# my1.net
KiCad netlist of a schematic drawn in EAGLE
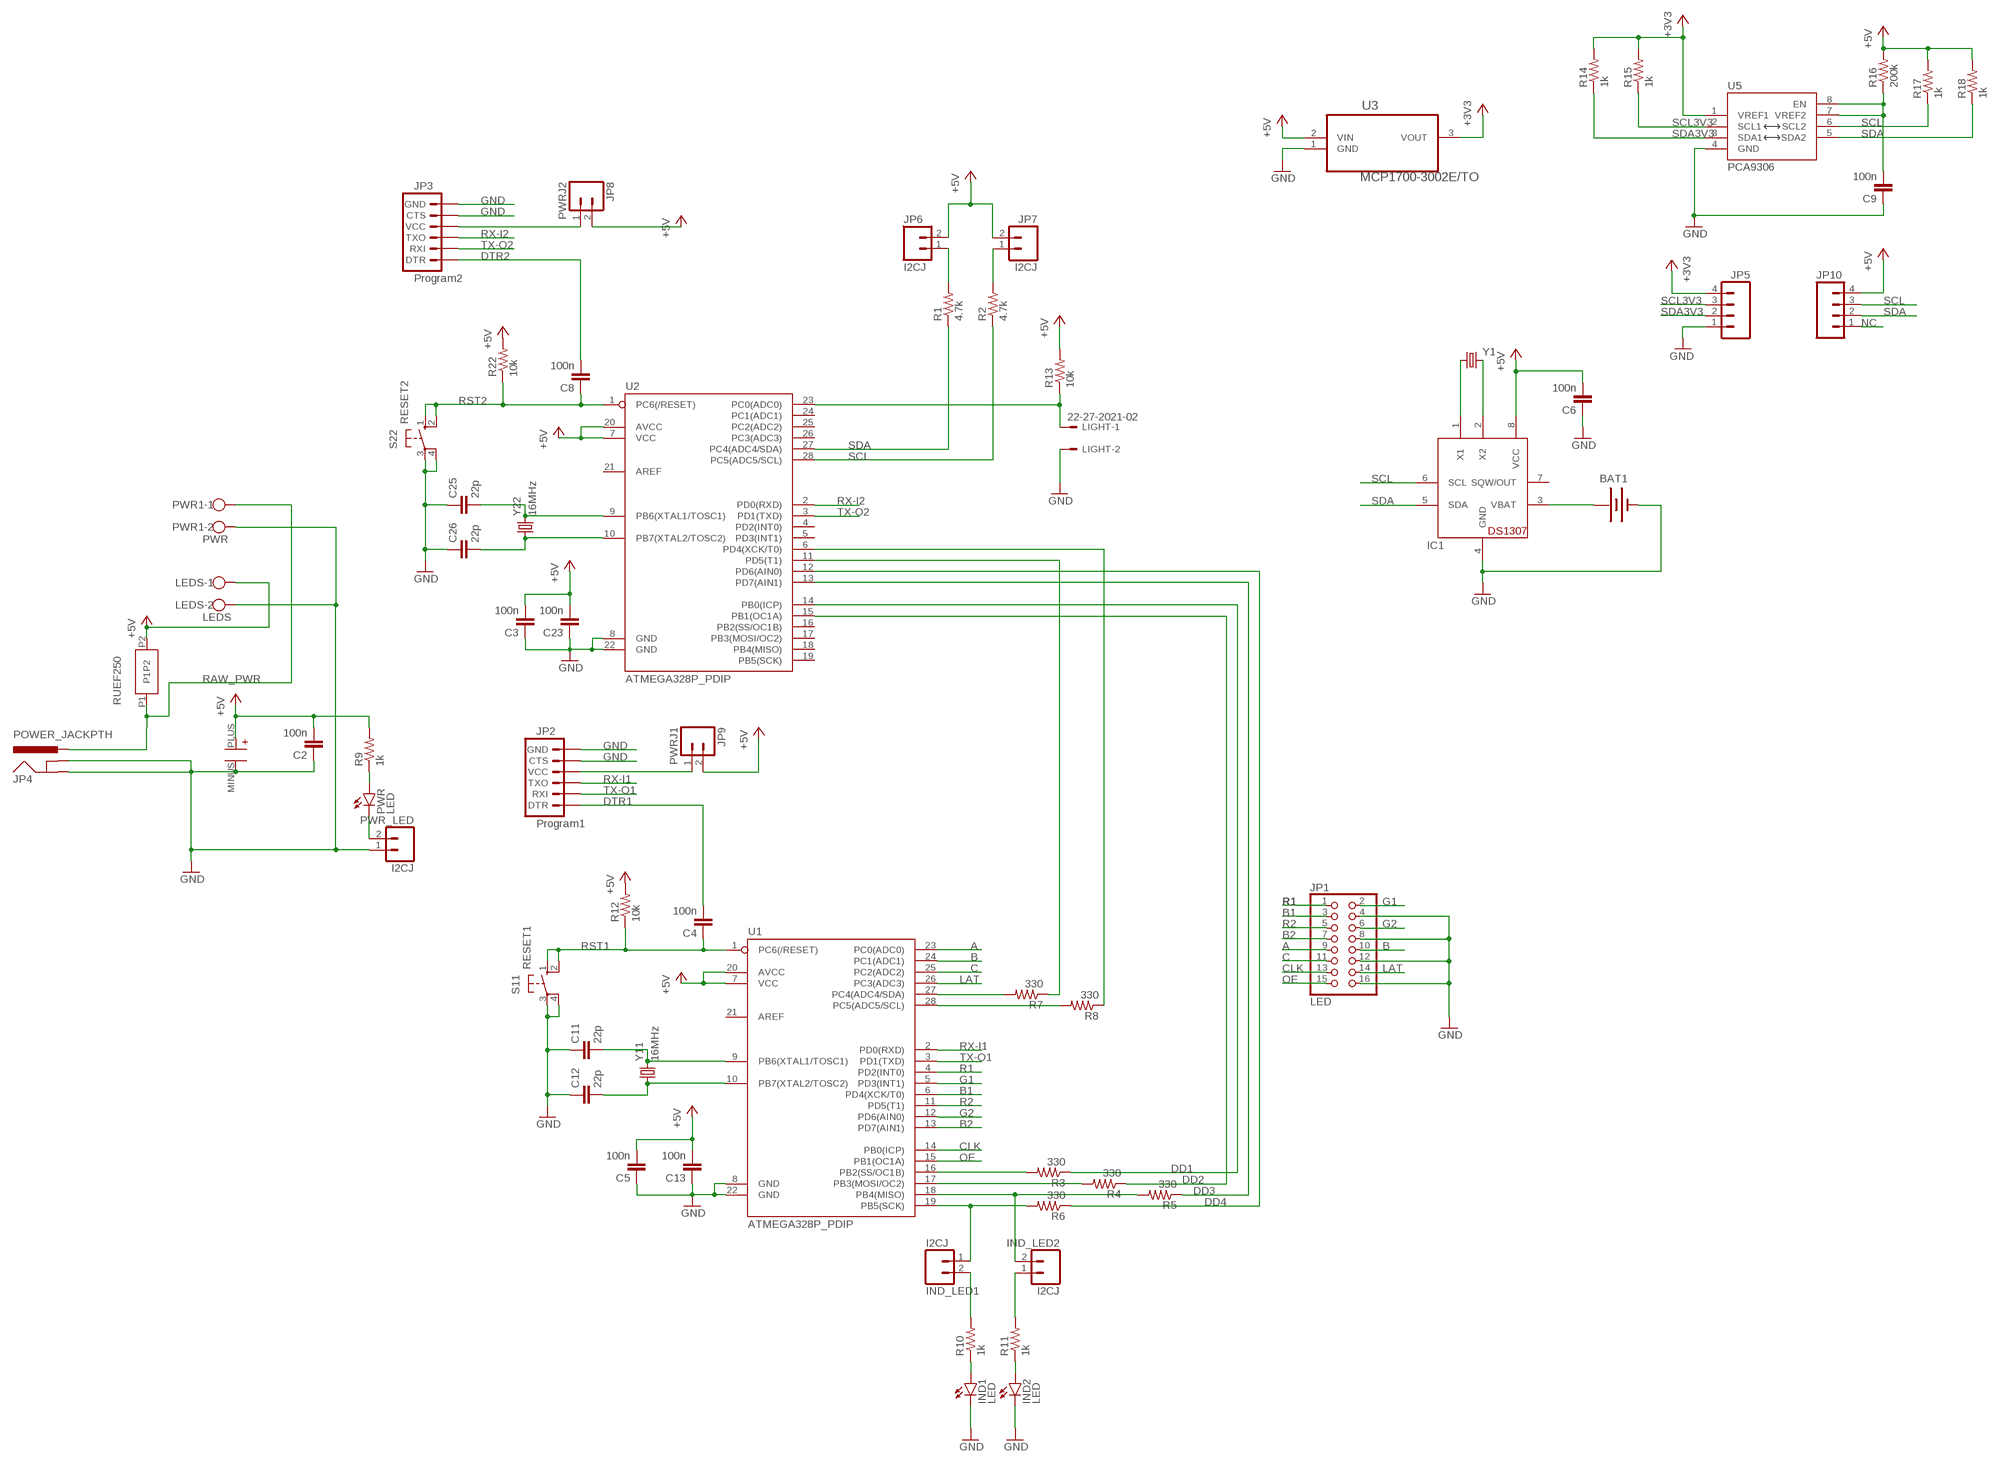
[diagram p0: schematic, sheet 1]

(export (version "E")
  (design (tool "Eeschema 10.0.6"))
  (components
    (comp (ref "BAT1")
      (value "BATTERY12MM")
      (footprint "eagle-import:BATTCON_12MM")
      (libsource (lib "eagle-import") (part "BATTERY12MM"))
    )
    (comp (ref "C1")
      (value "EEU-FR1C471B")
      (footprint "eagle-import:EEU-FR1C471B")
      (libsource (lib "eagle-import") (part "EEU-FR1C471B"))
    )
    (comp (ref "C2")
      (value "100n")
      (footprint "eagle-import:C025-024X044")
      (libsource (lib "eagle-import") (part "C-EU025-024X044"))
    )
    (comp (ref "C3")
      (value "100n")
      (footprint "eagle-import:C025-024X044")
      (libsource (lib "eagle-import") (part "C-EU025-024X044"))
    )
    (comp (ref "C4")
      (value "100n")
      (footprint "eagle-import:C025-024X044")
      (libsource (lib "eagle-import") (part "C-EU025-024X044"))
    )
    (comp (ref "C5")
      (value "100n")
      (footprint "eagle-import:C025-024X044")
      (libsource (lib "eagle-import") (part "C-EU025-024X044"))
    )
    (comp (ref "C6")
      (value "100n")
      (footprint "eagle-import:C025-024X044")
      (libsource (lib "eagle-import") (part "C-EU025-024X044"))
    )
    (comp (ref "C8")
      (value "100n")
      (footprint "eagle-import:C025-024X044")
      (libsource (lib "eagle-import") (part "C-EU025-024X044"))
    )
    (comp (ref "C9")
      (value "100n")
      (footprint "eagle-import:C025-024X044")
      (libsource (lib "eagle-import") (part "C-EU025-024X044"))
    )
    (comp (ref "C11")
      (value "22p")
      (footprint "eagle-import:C025-024X044")
      (libsource (lib "eagle-import") (part "C-EU025-024X044"))
    )
    (comp (ref "C12")
      (value "22p")
      (footprint "eagle-import:C025-024X044")
      (libsource (lib "eagle-import") (part "C-EU025-024X044"))
    )
    (comp (ref "C13")
      (value "100n")
      (footprint "eagle-import:C025-024X044")
      (libsource (lib "eagle-import") (part "C-EU025-024X044"))
    )
    (comp (ref "C23")
      (value "100n")
      (footprint "eagle-import:C025-024X044")
      (libsource (lib "eagle-import") (part "C-EU025-024X044"))
    )
    (comp (ref "C25")
      (value "22p")
      (footprint "eagle-import:C025-024X044")
      (libsource (lib "eagle-import") (part "C-EU025-024X044"))
    )
    (comp (ref "C26")
      (value "22p")
      (footprint "eagle-import:C025-024X044")
      (libsource (lib "eagle-import") (part "C-EU025-024X044"))
    )
    (comp (ref "IC1")
      (value "DS1307")
      (footprint "eagle-import:DIL08")
      (libsource (lib "eagle-import") (part "DS1307"))
    )
    (comp (ref "IND1")
      (value "LED")
      (footprint "eagle-import:LED5MM")
      (libsource (lib "eagle-import") (part "LED5MM"))
    )
    (comp (ref "IND2")
      (value "LED")
      (footprint "eagle-import:LED5MM")
      (libsource (lib "eagle-import") (part "LED5MM"))
    )
    (comp (ref "IND_LED1")
      (value "I2CJ")
      (footprint "eagle-import:1X02")
      (libsource (lib "eagle-import") (part "M02PTH"))
    )
    (comp (ref "IND_LED2")
      (value "I2CJ")
      (footprint "eagle-import:1X02")
      (libsource (lib "eagle-import") (part "M02PTH"))
    )
    (comp (ref "JP1")
      (value "LED")
      (footprint "eagle-import:2X08")
      (libsource (lib "eagle-import") (part "PINHD-2X8"))
    )
    (comp (ref "JP2")
      (value "Program1")
      (footprint "eagle-import:1X06")
      (libsource (lib "eagle-import") (part "ARDUINO_SERIAL_PROGRAMPTH"))
    )
    (comp (ref "JP3")
      (value "Program2")
      (footprint "eagle-import:1X06")
      (libsource (lib "eagle-import") (part "ARDUINO_SERIAL_PROGRAMPTH"))
    )
    (comp (ref "JP4")
      (value "POWER_JACKPTH")
      (footprint "eagle-import:POWER_JACK_PTH")
      (libsource (lib "eagle-import") (part "POWER_JACKPTH"))
    )
    (comp (ref "JP5")
      (value "M04PTH")
      (footprint "eagle-import:1X04")
      (libsource (lib "eagle-import") (part "M04PTH"))
    )
    (comp (ref "JP6")
      (value "I2CJ")
      (footprint "eagle-import:1X02")
      (libsource (lib "eagle-import") (part "M02PTH"))
    )
    (comp (ref "JP7")
      (value "I2CJ")
      (footprint "eagle-import:1X02")
      (libsource (lib "eagle-import") (part "M02PTH"))
    )
    (comp (ref "JP8")
      (value "PWRJ2")
      (footprint "eagle-import:1X02")
      (libsource (lib "eagle-import") (part "M02PTH"))
    )
    (comp (ref "JP9")
      (value "PWRJ1")
      (footprint "eagle-import:1X02")
      (libsource (lib "eagle-import") (part "M02PTH"))
    )
    (comp (ref "JP10")
      (value "M04PTH")
      (footprint "eagle-import:1X04")
      (libsource (lib "eagle-import") (part "M04PTH"))
    )
    (comp (ref "LEDS")
      (value "LEDS")
      (footprint "eagle-import:W237-102")
      (fields (field (name "MPN") "237-102"))
      (libsource (lib "eagle-import") (part "W237-102"))
    )
    (comp (ref "LIGHT")
      (value "22-27-2021-02")
      (footprint "eagle-import:6410-02")
      (libsource (lib "eagle-import") (part "22-?-0227-2021"))
    )
    (comp (ref "PWR")
      (value "LED")
      (footprint "eagle-import:LED5MM")
      (libsource (lib "eagle-import") (part "LED5MM"))
    )
    (comp (ref "PWR1")
      (value "PWR")
      (footprint "eagle-import:W237-102")
      (fields (field (name "MPN") "237-102"))
      (libsource (lib "eagle-import") (part "W237-102"))
    )
    (comp (ref "PWR_LED")
      (value "I2CJ")
      (footprint "eagle-import:1X02")
      (libsource (lib "eagle-import") (part "M02PTH"))
    )
    (comp (ref "R1")
      (value "4.7k")
      (footprint "eagle-import:AXIAL-0.3")
      (libsource (lib "eagle-import") (part "RESISTORAXIAL-0.3"))
    )
    (comp (ref "R2")
      (value "4.7k")
      (footprint "eagle-import:AXIAL-0.3")
      (libsource (lib "eagle-import") (part "RESISTORAXIAL-0.3"))
    )
    (comp (ref "R3")
      (value "330")
      (footprint "eagle-import:AXIAL-0.3")
      (libsource (lib "eagle-import") (part "RESISTORAXIAL-0.3"))
    )
    (comp (ref "R4")
      (value "330")
      (footprint "eagle-import:AXIAL-0.3")
      (libsource (lib "eagle-import") (part "RESISTORAXIAL-0.3"))
    )
    (comp (ref "R5")
      (value "330")
      (footprint "eagle-import:AXIAL-0.3")
      (libsource (lib "eagle-import") (part "RESISTORAXIAL-0.3"))
    )
    (comp (ref "R6")
      (value "330")
      (footprint "eagle-import:AXIAL-0.3")
      (libsource (lib "eagle-import") (part "RESISTORAXIAL-0.3"))
    )
    (comp (ref "R7")
      (value "330")
      (footprint "eagle-import:AXIAL-0.3")
      (libsource (lib "eagle-import") (part "RESISTORAXIAL-0.3"))
    )
    (comp (ref "R8")
      (value "330")
      (footprint "eagle-import:AXIAL-0.3")
      (libsource (lib "eagle-import") (part "RESISTORAXIAL-0.3"))
    )
    (comp (ref "R9")
      (value "1k")
      (footprint "eagle-import:AXIAL-0.3")
      (libsource (lib "eagle-import") (part "RESISTORAXIAL-0.3"))
    )
    (comp (ref "R10")
      (value "1k")
      (footprint "eagle-import:AXIAL-0.3")
      (libsource (lib "eagle-import") (part "RESISTORAXIAL-0.3"))
    )
    (comp (ref "R11")
      (value "1k")
      (footprint "eagle-import:AXIAL-0.3")
      (libsource (lib "eagle-import") (part "RESISTORAXIAL-0.3"))
    )
    (comp (ref "R12")
      (value "10k")
      (footprint "eagle-import:AXIAL-0.3")
      (libsource (lib "eagle-import") (part "RESISTORAXIAL-0.3"))
    )
    (comp (ref "R13")
      (value "10k")
      (footprint "eagle-import:AXIAL-0.3")
      (libsource (lib "eagle-import") (part "RESISTORAXIAL-0.3"))
    )
    (comp (ref "R14")
      (value "1k")
      (footprint "eagle-import:AXIAL-0.3")
      (libsource (lib "eagle-import") (part "RESISTORAXIAL-0.3"))
    )
    (comp (ref "R15")
      (value "1k")
      (footprint "eagle-import:AXIAL-0.3")
      (libsource (lib "eagle-import") (part "RESISTORAXIAL-0.3"))
    )
    (comp (ref "R16")
      (value "200k")
      (footprint "eagle-import:AXIAL-0.3")
      (libsource (lib "eagle-import") (part "RESISTORAXIAL-0.3"))
    )
    (comp (ref "R17")
      (value "1k")
      (footprint "eagle-import:AXIAL-0.3")
      (libsource (lib "eagle-import") (part "RESISTORAXIAL-0.3"))
    )
    (comp (ref "R18")
      (value "1k")
      (footprint "eagle-import:AXIAL-0.3")
      (libsource (lib "eagle-import") (part "RESISTORAXIAL-0.3"))
    )
    (comp (ref "R22")
      (value "10k")
      (footprint "eagle-import:AXIAL-0.3")
      (libsource (lib "eagle-import") (part "RESISTORAXIAL-0.3"))
    )
    (comp (ref "RUEF250")
      (value "RUEF250U")
      (footprint "eagle-import:RUEF250U")
      (libsource (lib "eagle-import") (part "RUEF250U"))
    )
    (comp (ref "S11")
      (value "RESET1")
      (footprint "eagle-import:B3F-10XX")
      (fields (field (name "MPN") "B3F-1000"))
      (libsource (lib "eagle-import") (part "10-XX"))
    )
    (comp (ref "S22")
      (value "RESET2")
      (footprint "eagle-import:B3F-10XX")
      (fields (field (name "MPN") "B3F-1000"))
      (libsource (lib "eagle-import") (part "10-XX"))
    )
    (comp (ref "U1")
      (value "ATMEGA328P_PDIP")
      (footprint "eagle-import:DIL28-3")
      (libsource (lib "eagle-import") (part "ATMEGA328P_PDIP"))
    )
    (comp (ref "U2")
      (value "ATMEGA328P_PDIP")
      (footprint "eagle-import:DIL28-3")
      (libsource (lib "eagle-import") (part "ATMEGA328P_PDIP"))
    )
    (comp (ref "U3")
      (value "MCP1700-3002E/TO")
      (footprint "eagle-import:TO127P254X495-3")
      (libsource (lib "eagle-import") (part "MCP1700-3002E/TO"))
    )
    (comp (ref "U5")
      (value "PCA9306")
      (footprint "eagle-import:PSOP-8")
      (libsource (lib "eagle-import") (part "PCA9306"))
    )
    (comp (ref "Y1")
      (value "CRYSTAL32-SMD")
      (footprint "eagle-import:CRYSTAL-32KHZ-SMD")
      (libsource (lib "eagle-import") (part "CRYSTAL32-SMD"))
    )
    (comp (ref "Y11")
      (value "16MHz")
      (footprint "eagle-import:HC49US")
      (libsource (lib "eagle-import") (part "CRYSTALHC49US"))
    )
    (comp (ref "Y22")
      (value "16MHz")
      (footprint "eagle-import:HC49US")
      (libsource (lib "eagle-import") (part "CRYSTALHC49US"))
    )
  )
  (nets
    (net (code "1") (name "+3V3") (class "Default")
      (node (ref "JP5") (pin "4") (pinfunction "4_4") (pintype "passive"))
      (node (ref "R14") (pin "P$2") (pinfunction "2_P$2") (pintype "passive"))
      (node (ref "R15") (pin "P$2") (pinfunction "2_P$2") (pintype "passive"))
      (node (ref "U3") (pin "3") (pinfunction "VOUT_3") (pintype "output"))
      (node (ref "U5") (pin "1") (pinfunction "VREF1_1") (pintype "bidirectional"))
    )
    (net (code "2") (name "+5V") (class "Default")
      (node (ref "C1") (pin "PLUS") (pinfunction "PLUS_PLUS") (pintype "bidirectional"))
      (node (ref "C13") (pin "2") (pinfunction "2_2") (pintype "passive"))
      (node (ref "C2") (pin "2") (pinfunction "2_2") (pintype "passive"))
      (node (ref "C23") (pin "2") (pinfunction "2_2") (pintype "passive"))
      (node (ref "C3") (pin "2") (pinfunction "2_2") (pintype "passive"))
      (node (ref "C5") (pin "2") (pinfunction "2_2") (pintype "passive"))
      (node (ref "C6") (pin "2") (pinfunction "2_2") (pintype "passive"))
      (node (ref "IC1") (pin "8") (pinfunction "VCC_8") (pintype "power_in"))
      (node (ref "JP10") (pin "4") (pinfunction "4_4") (pintype "passive"))
      (node (ref "JP6") (pin "2") (pinfunction "2_2") (pintype "passive"))
      (node (ref "JP7") (pin "2") (pinfunction "2_2") (pintype "passive"))
      (node (ref "JP8") (pin "2") (pinfunction "2_2") (pintype "passive"))
      (node (ref "JP9") (pin "2") (pinfunction "2_2") (pintype "passive"))
      (node (ref "LEDS") (pin "1") (pinfunction "KL_1") (pintype "passive"))
      (node (ref "R12") (pin "P$2") (pinfunction "2_P$2") (pintype "passive"))
      (node (ref "R13") (pin "P$2") (pinfunction "2_P$2") (pintype "passive"))
      (node (ref "R16") (pin "P$2") (pinfunction "2_P$2") (pintype "passive"))
      (node (ref "R17") (pin "P$2") (pinfunction "2_P$2") (pintype "passive"))
      (node (ref "R18") (pin "P$2") (pinfunction "2_P$2") (pintype "passive"))
      (node (ref "R22") (pin "P$2") (pinfunction "2_P$2") (pintype "passive"))
      (node (ref "R9") (pin "P$2") (pinfunction "2_P$2") (pintype "passive"))
      (node (ref "RUEF250") (pin "P2") (pinfunction "P2_P2") (pintype "bidirectional"))
      (node (ref "U1") (pin "20") (pinfunction "AVCC_20") (pintype "bidirectional"))
      (node (ref "U1") (pin "7") (pinfunction "VCC_7") (pintype "bidirectional"))
      (node (ref "U2") (pin "20") (pinfunction "AVCC_20") (pintype "bidirectional"))
      (node (ref "U2") (pin "7") (pinfunction "VCC_7") (pintype "bidirectional"))
      (node (ref "U3") (pin "2") (pinfunction "VIN_2") (pintype "input"))
    )
    (net (code "3") (name "/A") (class "Default")
      (node (ref "JP1") (pin "9") (pinfunction "9_9") (pintype "passive"))
      (node (ref "U1") (pin "23") (pinfunction "PC0(ADC0)_23") (pintype "bidirectional"))
    )
    (net (code "4") (name "/B") (class "Default")
      (node (ref "JP1") (pin "10") (pinfunction "10_10") (pintype "passive"))
      (node (ref "U1") (pin "24") (pinfunction "PC1(ADC1)_24") (pintype "bidirectional"))
    )
    (net (code "5") (name "/B1") (class "Default")
      (node (ref "JP1") (pin "3") (pinfunction "3_3") (pintype "passive"))
      (node (ref "U1") (pin "6") (pinfunction "PD4(XCK/T0)_6") (pintype "bidirectional"))
    )
    (net (code "6") (name "/B2") (class "Default")
      (node (ref "JP1") (pin "7") (pinfunction "7_7") (pintype "passive"))
      (node (ref "U1") (pin "13") (pinfunction "PD7(AIN1)_13") (pintype "bidirectional"))
    )
    (net (code "7") (name "/C") (class "Default")
      (node (ref "JP1") (pin "11") (pinfunction "11_11") (pintype "passive"))
      (node (ref "U1") (pin "25") (pinfunction "PC2(ADC2)_25") (pintype "bidirectional"))
    )
    (net (code "8") (name "/CLK") (class "Default")
      (node (ref "JP1") (pin "13") (pinfunction "13_13") (pintype "passive"))
      (node (ref "U1") (pin "14") (pinfunction "PB0(ICP)_14") (pintype "bidirectional"))
    )
    (net (code "9") (name "/DD1") (class "Default")
      (node (ref "R3") (pin "P$1") (pinfunction "1_P$1") (pintype "passive"))
      (node (ref "U2") (pin "14") (pinfunction "PB0(ICP)_14") (pintype "bidirectional"))
    )
    (net (code "10") (name "/DD2") (class "Default")
      (node (ref "R4") (pin "P$1") (pinfunction "1_P$1") (pintype "passive"))
      (node (ref "U2") (pin "15") (pinfunction "PB1(OC1A)_15") (pintype "bidirectional"))
    )
    (net (code "11") (name "/DD3") (class "Default")
      (node (ref "R5") (pin "P$1") (pinfunction "1_P$1") (pintype "passive"))
      (node (ref "U2") (pin "13") (pinfunction "PD7(AIN1)_13") (pintype "bidirectional"))
    )
    (net (code "12") (name "/DD4") (class "Default")
      (node (ref "R6") (pin "P$1") (pinfunction "1_P$1") (pintype "passive"))
      (node (ref "U2") (pin "12") (pinfunction "PD6(AIN0)_12") (pintype "bidirectional"))
    )
    (net (code "13") (name "/DTR1") (class "Default")
      (node (ref "C4") (pin "2") (pinfunction "2_2") (pintype "passive"))
      (node (ref "JP2") (pin "1") (pinfunction "DTR_1") (pintype "passive"))
    )
    (net (code "14") (name "/DTR2") (class "Default")
      (node (ref "C8") (pin "2") (pinfunction "2_2") (pintype "passive"))
      (node (ref "JP3") (pin "1") (pinfunction "DTR_1") (pintype "passive"))
    )
    (net (code "15") (name "/G1") (class "Default")
      (node (ref "JP1") (pin "2") (pinfunction "2_2") (pintype "passive"))
      (node (ref "U1") (pin "5") (pinfunction "PD3(INT1)_5") (pintype "bidirectional"))
    )
    (net (code "16") (name "/G2") (class "Default")
      (node (ref "JP1") (pin "6") (pinfunction "6_6") (pintype "passive"))
      (node (ref "U1") (pin "12") (pinfunction "PD6(AIN0)_12") (pintype "bidirectional"))
    )
    (net (code "17") (name "/LAT") (class "Default")
      (node (ref "JP1") (pin "14") (pinfunction "14_14") (pintype "passive"))
      (node (ref "U1") (pin "26") (pinfunction "PC3(ADC3)_26") (pintype "bidirectional"))
    )
    (net (code "18") (name "/NC") (class "Default")
      (node (ref "JP10") (pin "1") (pinfunction "1_1") (pintype "passive"))
    )
    (net (code "19") (name "/OE") (class "Default")
      (node (ref "JP1") (pin "15") (pinfunction "15_15") (pintype "passive"))
      (node (ref "U1") (pin "15") (pinfunction "PB1(OC1A)_15") (pintype "bidirectional"))
    )
    (net (code "20") (name "/R1") (class "Default")
      (node (ref "JP1") (pin "1") (pinfunction "1_1") (pintype "passive"))
      (node (ref "U1") (pin "4") (pinfunction "PD2(INT0)_4") (pintype "bidirectional"))
    )
    (net (code "21") (name "/R2") (class "Default")
      (node (ref "JP1") (pin "5") (pinfunction "5_5") (pintype "passive"))
      (node (ref "U1") (pin "11") (pinfunction "PD5(T1)_11") (pintype "bidirectional"))
    )
    (net (code "22") (name "/RAW_PWR") (class "Default")
      (node (ref "JP4") (pin "PWR") (pinfunction "PWR_PWR") (pintype "bidirectional"))
      (node (ref "PWR1") (pin "1") (pinfunction "KL_1") (pintype "passive"))
      (node (ref "RUEF250") (pin "P1") (pinfunction "P1_P1") (pintype "bidirectional"))
    )
    (net (code "23") (name "/RST1") (class "Default")
      (node (ref "C4") (pin "1") (pinfunction "1_1") (pintype "passive"))
      (node (ref "R12") (pin "P$1") (pinfunction "1_P$1") (pintype "passive"))
      (node (ref "S11") (pin "1") (pinfunction "S_1") (pintype "passive"))
      (node (ref "S11") (pin "2") (pinfunction "S1_2") (pintype "passive"))
      (node (ref "U1") (pin "1") (pinfunction "PC6(/RESET)_1") (pintype "bidirectional"))
    )
    (net (code "24") (name "/RST2") (class "Default")
      (node (ref "C8") (pin "1") (pinfunction "1_1") (pintype "passive"))
      (node (ref "R22") (pin "P$1") (pinfunction "1_P$1") (pintype "passive"))
      (node (ref "S22") (pin "1") (pinfunction "S_1") (pintype "passive"))
      (node (ref "S22") (pin "2") (pinfunction "S1_2") (pintype "passive"))
      (node (ref "U2") (pin "1") (pinfunction "PC6(/RESET)_1") (pintype "bidirectional"))
    )
    (net (code "25") (name "/RX-I1") (class "Default")
      (node (ref "JP2") (pin "3") (pinfunction "TXO_3") (pintype "passive"))
      (node (ref "U1") (pin "2") (pinfunction "PD0(RXD)_2") (pintype "bidirectional"))
    )
    (net (code "26") (name "/RX-I2") (class "Default")
      (node (ref "JP3") (pin "3") (pinfunction "TXO_3") (pintype "passive"))
      (node (ref "U2") (pin "2") (pinfunction "PD0(RXD)_2") (pintype "bidirectional"))
    )
    (net (code "27") (name "/SCL") (class "Default")
      (node (ref "IC1") (pin "6") (pinfunction "SCL_6") (pintype "bidirectional"))
      (node (ref "JP10") (pin "3") (pinfunction "3_3") (pintype "passive"))
      (node (ref "R17") (pin "P$1") (pinfunction "1_P$1") (pintype "passive"))
      (node (ref "R2") (pin "P$1") (pinfunction "1_P$1") (pintype "passive"))
      (node (ref "U2") (pin "28") (pinfunction "PC5(ADC5/SCL)_28") (pintype "bidirectional"))
      (node (ref "U5") (pin "6") (pinfunction "SCL2_6") (pintype "bidirectional"))
    )
    (net (code "28") (name "/SCL3V3") (class "Default")
      (node (ref "JP5") (pin "3") (pinfunction "3_3") (pintype "passive"))
      (node (ref "R15") (pin "P$1") (pinfunction "1_P$1") (pintype "passive"))
      (node (ref "U5") (pin "2") (pinfunction "SCL1_2") (pintype "bidirectional"))
    )
    (net (code "29") (name "/SDA") (class "Default")
      (node (ref "IC1") (pin "5") (pinfunction "SDA_5") (pintype "bidirectional"))
      (node (ref "JP10") (pin "2") (pinfunction "2_2") (pintype "passive"))
      (node (ref "R1") (pin "P$1") (pinfunction "1_P$1") (pintype "passive"))
      (node (ref "R18") (pin "P$1") (pinfunction "1_P$1") (pintype "passive"))
      (node (ref "U2") (pin "27") (pinfunction "PC4(ADC4/SDA)_27") (pintype "bidirectional"))
      (node (ref "U5") (pin "5") (pinfunction "SDA2_5") (pintype "bidirectional"))
    )
    (net (code "30") (name "/SDA3V3") (class "Default")
      (node (ref "JP5") (pin "2") (pinfunction "2_2") (pintype "passive"))
      (node (ref "R14") (pin "P$1") (pinfunction "1_P$1") (pintype "passive"))
      (node (ref "U5") (pin "3") (pinfunction "SDA1_3") (pintype "bidirectional"))
    )
    (net (code "31") (name "/TX-O1") (class "Default")
      (node (ref "JP2") (pin "2") (pinfunction "RXI_2") (pintype "passive"))
      (node (ref "U1") (pin "3") (pinfunction "PD1(TXD)_3") (pintype "bidirectional"))
    )
    (net (code "32") (name "/TX-O2") (class "Default")
      (node (ref "JP3") (pin "2") (pinfunction "RXI_2") (pintype "passive"))
      (node (ref "U2") (pin "3") (pinfunction "PD1(TXD)_3") (pintype "bidirectional"))
    )
    (net (code "33") (name "GND") (class "Default")
      (node (ref "BAT1") (pin "GND") (pinfunction "-_GND") (pintype "power_in"))
      (node (ref "C1") (pin "MINUS") (pinfunction "MINUS_MINUS") (pintype "bidirectional"))
      (node (ref "C11") (pin "1") (pinfunction "1_1") (pintype "passive"))
      (node (ref "C12") (pin "1") (pinfunction "1_1") (pintype "passive"))
      (node (ref "C13") (pin "1") (pinfunction "1_1") (pintype "passive"))
      (node (ref "C2") (pin "1") (pinfunction "1_1") (pintype "passive"))
      (node (ref "C23") (pin "1") (pinfunction "1_1") (pintype "passive"))
      (node (ref "C25") (pin "1") (pinfunction "1_1") (pintype "passive"))
      (node (ref "C26") (pin "1") (pinfunction "1_1") (pintype "passive"))
      (node (ref "C3") (pin "1") (pinfunction "1_1") (pintype "passive"))
      (node (ref "C5") (pin "1") (pinfunction "1_1") (pintype "passive"))
      (node (ref "C6") (pin "1") (pinfunction "1_1") (pintype "passive"))
      (node (ref "C9") (pin "1") (pinfunction "1_1") (pintype "passive"))
      (node (ref "IC1") (pin "4") (pinfunction "GND_4") (pintype "power_in"))
      (node (ref "IND1") (pin "K") (pinfunction "C_K") (pintype "passive"))
      (node (ref "IND2") (pin "K") (pinfunction "C_K") (pintype "passive"))
      (node (ref "JP1") (pin "12") (pinfunction "12_12") (pintype "passive"))
      (node (ref "JP1") (pin "16") (pinfunction "16_16") (pintype "passive"))
      (node (ref "JP1") (pin "4") (pinfunction "4_4") (pintype "passive"))
      (node (ref "JP1") (pin "8") (pinfunction "8_8") (pintype "passive"))
      (node (ref "JP2") (pin "5") (pinfunction "CTS_5") (pintype "passive"))
      (node (ref "JP2") (pin "6") (pinfunction "GND_6") (pintype "passive"))
      (node (ref "JP3") (pin "5") (pinfunction "CTS_5") (pintype "passive"))
      (node (ref "JP3") (pin "6") (pinfunction "GND_6") (pintype "passive"))
      (node (ref "JP4") (pin "GND") (pinfunction "GND_GND") (pintype "bidirectional"))
      (node (ref "JP4") (pin "GNDBREAK") (pinfunction "GNDBREAK_GNDBREAK") (pintype "bidirectional"))
      (node (ref "JP5") (pin "1") (pinfunction "1_1") (pintype "passive"))
      (node (ref "LEDS") (pin "2") (pinfunction "KL_2") (pintype "passive"))
      (node (ref "LIGHT") (pin "2") (pinfunction "S_2") (pintype "passive"))
      (node (ref "PWR1") (pin "2") (pinfunction "KL_2") (pintype "passive"))
      (node (ref "PWR_LED") (pin "1") (pinfunction "1_1") (pintype "passive"))
      (node (ref "S11") (pin "3") (pinfunction "P_3") (pintype "passive"))
      (node (ref "S11") (pin "4") (pinfunction "P1_4") (pintype "passive"))
      (node (ref "S22") (pin "3") (pinfunction "P_3") (pintype "passive"))
      (node (ref "S22") (pin "4") (pinfunction "P1_4") (pintype "passive"))
      (node (ref "U1") (pin "22") (pinfunction "GND_22") (pintype "bidirectional"))
      (node (ref "U1") (pin "8") (pinfunction "GND_8") (pintype "bidirectional"))
      (node (ref "U2") (pin "22") (pinfunction "GND_22") (pintype "bidirectional"))
      (node (ref "U2") (pin "8") (pinfunction "GND_8") (pintype "bidirectional"))
      (node (ref "U3") (pin "1") (pinfunction "GND_1") (pintype "passive"))
      (node (ref "U5") (pin "4") (pinfunction "GND_4") (pintype "bidirectional"))
    )
    (net (code "34") (name "Net-(BAT1-+)") (class "Default")
      (node (ref "BAT1") (pin "PWR@1") (pinfunction "+_PWR@1") (pintype "power_in"))
      (node (ref "IC1") (pin "3") (pinfunction "VBAT_3") (pintype "power_in"))
    )
    (net (code "35") (name "Net-(IC1-X1)") (class "Default")
      (node (ref "IC1") (pin "1") (pinfunction "X1_1") (pintype "passive"))
      (node (ref "Y1") (pin "X1") (pinfunction "1_X1") (pintype "passive"))
    )
    (net (code "36") (name "Net-(IC1-X2)") (class "Default")
      (node (ref "IC1") (pin "2") (pinfunction "X2_2") (pintype "passive"))
      (node (ref "Y1") (pin "X2") (pinfunction "2_X2") (pintype "passive"))
    )
    (net (code "37") (name "Net-(JP2-VCC)") (class "Default")
      (node (ref "JP2") (pin "4") (pinfunction "VCC_4") (pintype "passive"))
      (node (ref "JP9") (pin "1") (pinfunction "1_1") (pintype "passive"))
    )
    (net (code "38") (name "Net-(JP3-VCC)") (class "Default")
      (node (ref "JP3") (pin "4") (pinfunction "VCC_4") (pintype "passive"))
      (node (ref "JP8") (pin "1") (pinfunction "1_1") (pintype "passive"))
    )
    (net (code "39") (name "Net-(LIGHTA-S)") (class "Default")
      (node (ref "LIGHT") (pin "1") (pinfunction "S_1") (pintype "passive"))
      (node (ref "R13") (pin "P$1") (pinfunction "1_P$1") (pintype "passive"))
      (node (ref "U2") (pin "23") (pinfunction "PC0(ADC0)_23") (pintype "bidirectional"))
    )
    (net (code "40") (name "Net-(PWR-C)") (class "Default")
      (node (ref "PWR") (pin "K") (pinfunction "C_K") (pintype "passive"))
      (node (ref "PWR_LED") (pin "2") (pinfunction "2_2") (pintype "passive"))
    )
    (net (code "41") (name "Net-(R1-2)") (class "Default")
      (node (ref "JP6") (pin "1") (pinfunction "1_1") (pintype "passive"))
      (node (ref "R1") (pin "P$2") (pinfunction "2_P$2") (pintype "passive"))
    )
    (net (code "42") (name "Net-(R2-2)") (class "Default")
      (node (ref "JP7") (pin "1") (pinfunction "1_1") (pintype "passive"))
      (node (ref "R2") (pin "P$2") (pinfunction "2_P$2") (pintype "passive"))
    )
    (net (code "43") (name "Net-(R3-2)") (class "Default")
      (node (ref "R3") (pin "P$2") (pinfunction "2_P$2") (pintype "passive"))
      (node (ref "U1") (pin "16") (pinfunction "PB2(SS/OC1B)_16") (pintype "bidirectional"))
    )
    (net (code "44") (name "Net-(R4-2)") (class "Default")
      (node (ref "R4") (pin "P$2") (pinfunction "2_P$2") (pintype "passive"))
      (node (ref "U1") (pin "17") (pinfunction "PB3(MOSI/OC2)_17") (pintype "bidirectional"))
    )
    (net (code "45") (name "Net-(R5-2)") (class "Default")
      (node (ref "IND_LED2") (pin "2") (pinfunction "2_2") (pintype "passive"))
      (node (ref "R5") (pin "P$2") (pinfunction "2_P$2") (pintype "passive"))
      (node (ref "U1") (pin "18") (pinfunction "PB4(MISO)_18") (pintype "bidirectional"))
    )
    (net (code "46") (name "Net-(R6-2)") (class "Default")
      (node (ref "IND_LED1") (pin "1") (pinfunction "1_1") (pintype "passive"))
      (node (ref "R6") (pin "P$2") (pinfunction "2_P$2") (pintype "passive"))
      (node (ref "U1") (pin "19") (pinfunction "PB5(SCK)_19") (pintype "bidirectional"))
    )
    (net (code "47") (name "Net-(R7-1)") (class "Default")
      (node (ref "R7") (pin "P$1") (pinfunction "1_P$1") (pintype "passive"))
      (node (ref "U2") (pin "11") (pinfunction "PD5(T1)_11") (pintype "bidirectional"))
    )
    (net (code "48") (name "Net-(R7-2)") (class "Default")
      (node (ref "R7") (pin "P$2") (pinfunction "2_P$2") (pintype "passive"))
      (node (ref "U1") (pin "27") (pinfunction "PC4(ADC4/SDA)_27") (pintype "bidirectional"))
    )
    (net (code "49") (name "Net-(R8-1)") (class "Default")
      (node (ref "R8") (pin "P$1") (pinfunction "1_P$1") (pintype "passive"))
      (node (ref "U2") (pin "6") (pinfunction "PD4(XCK/T0)_6") (pintype "bidirectional"))
    )
    (net (code "50") (name "Net-(R8-2)") (class "Default")
      (node (ref "R8") (pin "P$2") (pinfunction "2_P$2") (pintype "passive"))
      (node (ref "U1") (pin "28") (pinfunction "PC5(ADC5/SCL)_28") (pintype "bidirectional"))
    )
    (net (code "51") (name "Net-(R9-1)") (class "Default")
      (node (ref "PWR") (pin "A") (pinfunction "A_A") (pintype "passive"))
      (node (ref "R9") (pin "P$1") (pinfunction "1_P$1") (pintype "passive"))
    )
    (net (code "52") (name "Net-(R10-1)") (class "Default")
      (node (ref "IND1") (pin "A") (pinfunction "A_A") (pintype "passive"))
      (node (ref "R10") (pin "P$1") (pinfunction "1_P$1") (pintype "passive"))
    )
    (net (code "53") (name "Net-(R10-2)") (class "Default")
      (node (ref "IND_LED1") (pin "2") (pinfunction "2_2") (pintype "passive"))
      (node (ref "R10") (pin "P$2") (pinfunction "2_P$2") (pintype "passive"))
    )
    (net (code "54") (name "Net-(R11-1)") (class "Default")
      (node (ref "IND2") (pin "A") (pinfunction "A_A") (pintype "passive"))
      (node (ref "R11") (pin "P$1") (pinfunction "1_P$1") (pintype "passive"))
    )
    (net (code "55") (name "Net-(R11-2)") (class "Default")
      (node (ref "IND_LED2") (pin "1") (pinfunction "1_1") (pintype "passive"))
      (node (ref "R11") (pin "P$2") (pinfunction "2_P$2") (pintype "passive"))
    )
    (net (code "56") (name "Net-(R16-1)") (class "Default")
      (node (ref "C9") (pin "2") (pinfunction "2_2") (pintype "passive"))
      (node (ref "R16") (pin "P$1") (pinfunction "1_P$1") (pintype "passive"))
      (node (ref "U5") (pin "7") (pinfunction "VREF2_7") (pintype "bidirectional"))
      (node (ref "U5") (pin "8") (pinfunction "EN_8") (pintype "bidirectional"))
    )
    (net (code "57") (name "Net-(U1-PB6(XTAL1{slash}TOSC1))") (class "Default")
      (node (ref "C11") (pin "2") (pinfunction "2_2") (pintype "passive"))
      (node (ref "U1") (pin "9") (pinfunction "PB6(XTAL1/TOSC1)_9") (pintype "bidirectional"))
      (node (ref "Y11") (pin "2") (pinfunction "2_2") (pintype "passive"))
    )
    (net (code "58") (name "Net-(U1-PB7(XTAL2{slash}TOSC2))") (class "Default")
      (node (ref "C12") (pin "2") (pinfunction "2_2") (pintype "passive"))
      (node (ref "U1") (pin "10") (pinfunction "PB7(XTAL2/TOSC2)_10") (pintype "bidirectional"))
      (node (ref "Y11") (pin "1") (pinfunction "1_1") (pintype "passive"))
    )
    (net (code "59") (name "Net-(U2-PB6(XTAL1{slash}TOSC1))") (class "Default")
      (node (ref "C25") (pin "2") (pinfunction "2_2") (pintype "passive"))
      (node (ref "U2") (pin "9") (pinfunction "PB6(XTAL1/TOSC1)_9") (pintype "bidirectional"))
      (node (ref "Y22") (pin "2") (pinfunction "2_2") (pintype "passive"))
    )
    (net (code "60") (name "Net-(U2-PB7(XTAL2{slash}TOSC2))") (class "Default")
      (node (ref "C26") (pin "2") (pinfunction "2_2") (pintype "passive"))
      (node (ref "U2") (pin "10") (pinfunction "PB7(XTAL2/TOSC2)_10") (pintype "bidirectional"))
      (node (ref "Y22") (pin "1") (pinfunction "1_1") (pintype "passive"))
    )
    (net (code "61") (name "unconnected-(IC1-SQW{slash}OUT-Pad7)") (class "Default")
      (node (ref "IC1") (pin "7") (pinfunction "SQW/OUT_7") (pintype "bidirectional"))
    )
    (net (code "62") (name "unconnected-(U1-AREF-Pad21)") (class "Default")
      (node (ref "U1") (pin "21") (pinfunction "AREF_21") (pintype "bidirectional"))
    )
    (net (code "63") (name "unconnected-(U2-AREF-Pad21)") (class "Default")
      (node (ref "U2") (pin "21") (pinfunction "AREF_21") (pintype "bidirectional"))
    )
    (net (code "64") (name "unconnected-(U2-PB2(SS{slash}OC1B)-Pad16)") (class "Default")
      (node (ref "U2") (pin "16") (pinfunction "PB2(SS/OC1B)_16") (pintype "bidirectional"))
    )
    (net (code "65") (name "unconnected-(U2-PB3(MOSI{slash}OC2)-Pad17)") (class "Default")
      (node (ref "U2") (pin "17") (pinfunction "PB3(MOSI/OC2)_17") (pintype "bidirectional"))
    )
    (net (code "66") (name "unconnected-(U2-PB4(MISO)-Pad18)") (class "Default")
      (node (ref "U2") (pin "18") (pinfunction "PB4(MISO)_18") (pintype "bidirectional"))
    )
    (net (code "67") (name "unconnected-(U2-PB5(SCK)-Pad19)") (class "Default")
      (node (ref "U2") (pin "19") (pinfunction "PB5(SCK)_19") (pintype "bidirectional"))
    )
    (net (code "68") (name "unconnected-(U2-PC1(ADC1)-Pad24)") (class "Default")
      (node (ref "U2") (pin "24") (pinfunction "PC1(ADC1)_24") (pintype "bidirectional"))
    )
    (net (code "69") (name "unconnected-(U2-PC2(ADC2)-Pad25)") (class "Default")
      (node (ref "U2") (pin "25") (pinfunction "PC2(ADC2)_25") (pintype "bidirectional"))
    )
    (net (code "70") (name "unconnected-(U2-PC3(ADC3)-Pad26)") (class "Default")
      (node (ref "U2") (pin "26") (pinfunction "PC3(ADC3)_26") (pintype "bidirectional"))
    )
    (net (code "71") (name "unconnected-(U2-PD2(INT0)-Pad4)") (class "Default")
      (node (ref "U2") (pin "4") (pinfunction "PD2(INT0)_4") (pintype "bidirectional"))
    )
    (net (code "72") (name "unconnected-(U2-PD3(INT1)-Pad5)") (class "Default")
      (node (ref "U2") (pin "5") (pinfunction "PD3(INT1)_5") (pintype "bidirectional"))
    )
  )
)
